# Pakfav7.net
KiCad netlist of a schematic drawn in EAGLE
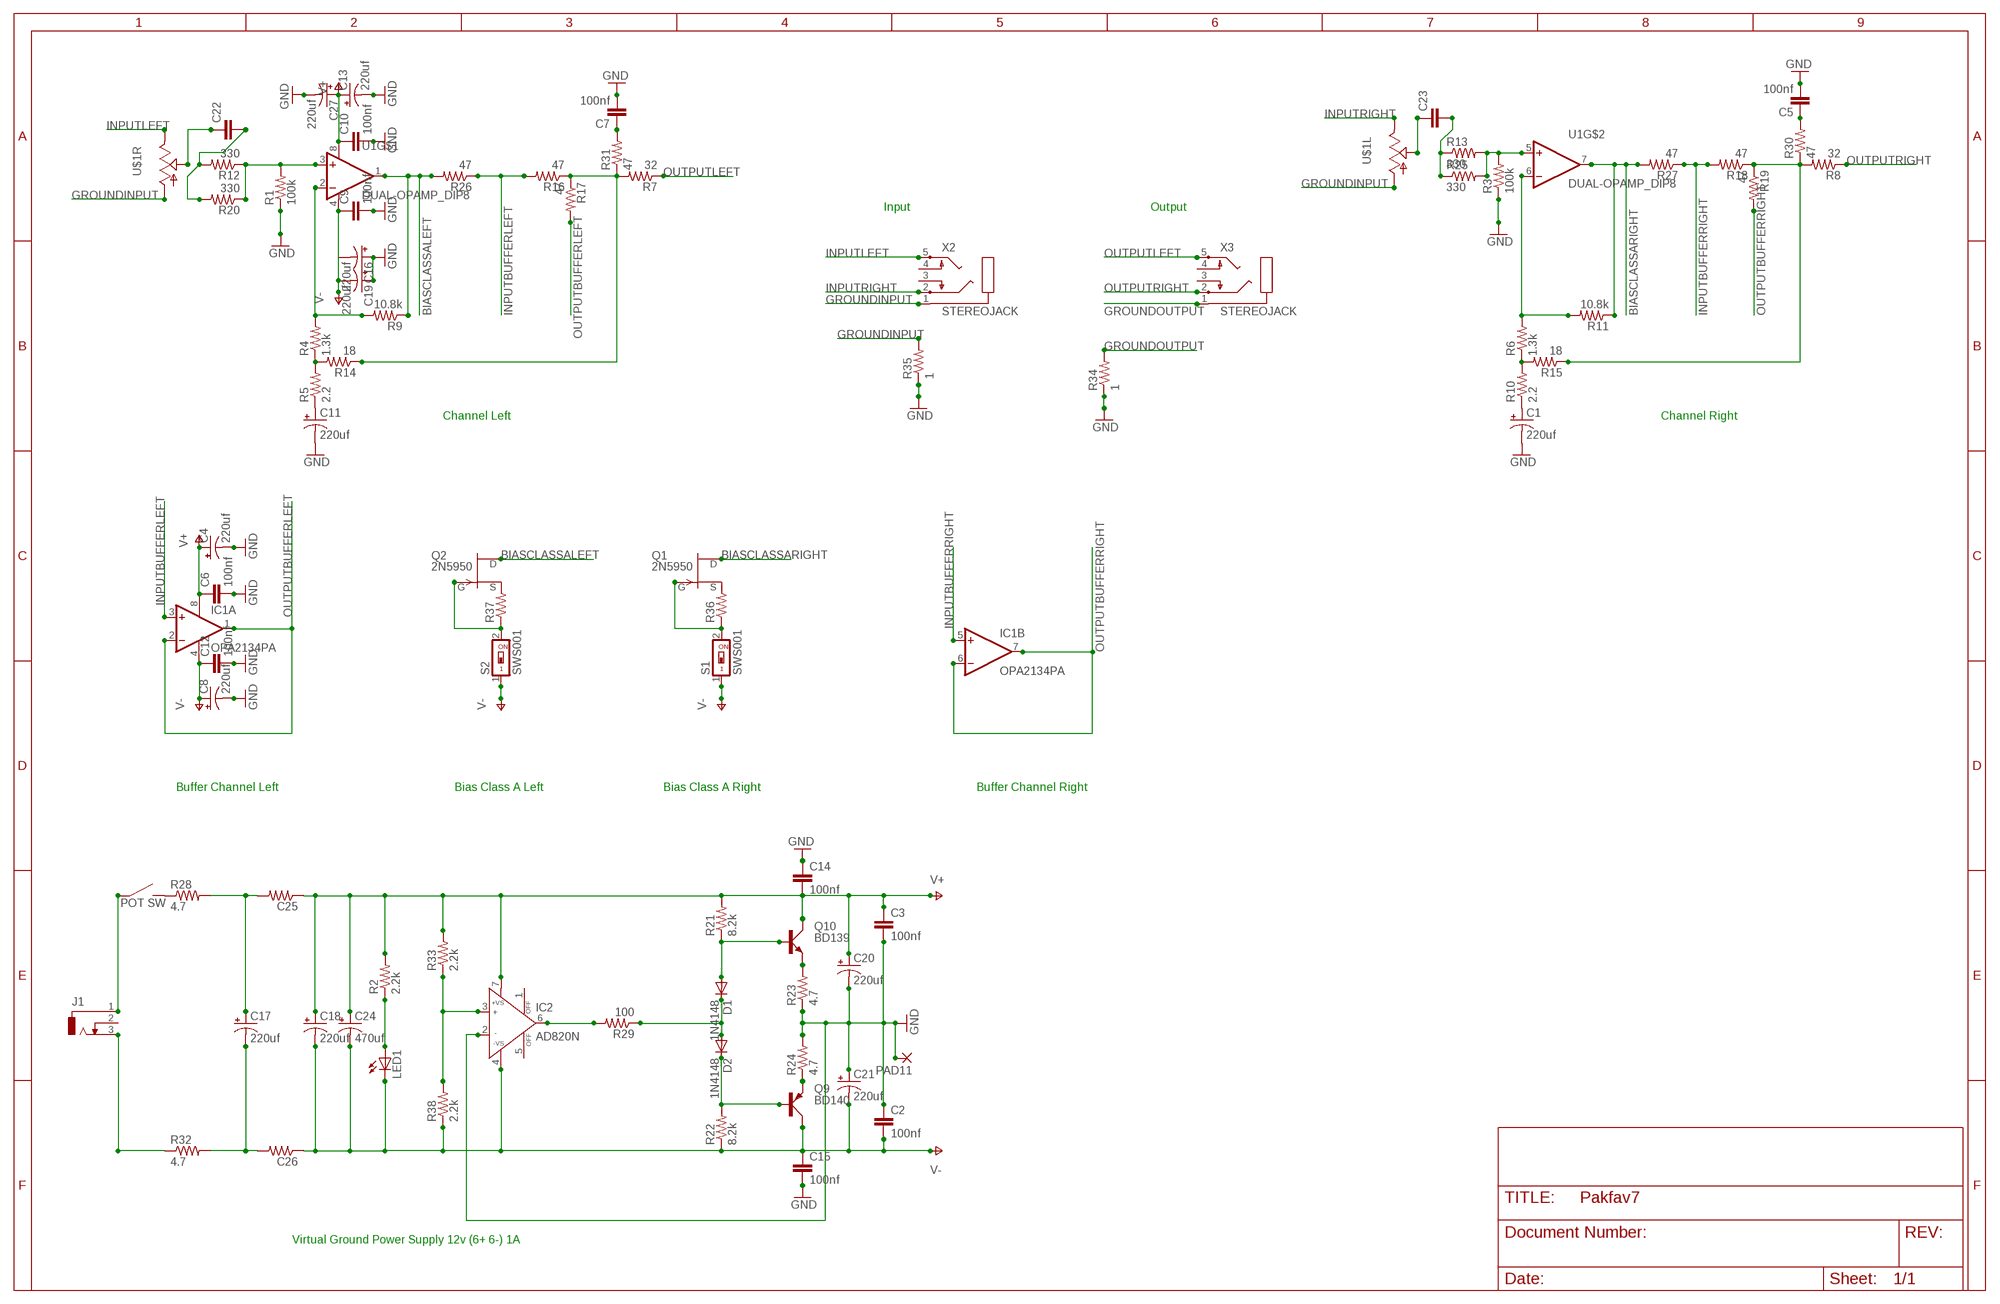
[diagram p0: schematic, sheet 1]

(export (version "E")
  (design (tool "Eeschema 10.0.6"))
  (components
    (comp (ref "C1")
      (value "220uf")
      (footprint "eagle-import:E5-10,5")
      (libsource (lib "eagle-import") (part "CPOL-USE5-10.5"))
    )
    (comp (ref "C2")
      (value "100nf")
      (footprint "eagle-import:C5B2.5")
      (libsource (lib "eagle-import") (part "C5/2.5"))
    )
    (comp (ref "C3")
      (value "100nf")
      (footprint "eagle-import:C5B2.5")
      (libsource (lib "eagle-import") (part "C5/2.5"))
    )
    (comp (ref "C4")
      (value "220uf")
      (footprint "eagle-import:E5-10,5")
      (libsource (lib "eagle-import") (part "CPOL-USE5-10.5"))
    )
    (comp (ref "C5")
      (value "100nf")
      (footprint "eagle-import:C5B2.5")
      (libsource (lib "eagle-import") (part "C5/2.5"))
    )
    (comp (ref "C6")
      (value "100nf")
      (footprint "eagle-import:C5B2.5")
      (libsource (lib "eagle-import") (part "C5/2.5"))
    )
    (comp (ref "C7")
      (value "100nf")
      (footprint "eagle-import:C5B2.5")
      (libsource (lib "eagle-import") (part "C5/2.5"))
    )
    (comp (ref "C8")
      (value "220uf")
      (footprint "eagle-import:E5-10,5")
      (libsource (lib "eagle-import") (part "CPOL-USE5-10.5"))
    )
    (comp (ref "C9")
      (value "100nf")
      (footprint "eagle-import:C5B2.5")
      (libsource (lib "eagle-import") (part "C5/2.5"))
    )
    (comp (ref "C10")
      (value "100nf")
      (footprint "eagle-import:C5B2.5")
      (libsource (lib "eagle-import") (part "C5/2.5"))
    )
    (comp (ref "C11")
      (value "220uf")
      (footprint "eagle-import:E5-10,5")
      (libsource (lib "eagle-import") (part "CPOL-USE5-10.5"))
    )
    (comp (ref "C12")
      (value "100nf")
      (footprint "eagle-import:C5B2.5")
      (libsource (lib "eagle-import") (part "C5/2.5"))
    )
    (comp (ref "C13")
      (value "220uf")
      (footprint "eagle-import:E5-10,5")
      (libsource (lib "eagle-import") (part "CPOL-USE5-10.5"))
    )
    (comp (ref "C14")
      (value "100nf")
      (footprint "eagle-import:C5B2.5")
      (libsource (lib "eagle-import") (part "C5/2.5"))
    )
    (comp (ref "C15")
      (value "100nf")
      (footprint "eagle-import:C5B2.5")
      (libsource (lib "eagle-import") (part "C5/2.5"))
    )
    (comp (ref "C16")
      (value "220uf")
      (footprint "eagle-import:E5-10,5")
      (libsource (lib "eagle-import") (part "CPOL-USE5-10.5"))
    )
    (comp (ref "C17")
      (value "220uf")
      (footprint "eagle-import:E3,5-10")
      (libsource (lib "eagle-import") (part "rcl_334_CPOL-USE3.5-10"))
    )
    (comp (ref "C18")
      (value "220uf")
      (footprint "eagle-import:E3,5-10")
      (libsource (lib "eagle-import") (part "rcl_334_CPOL-USE3.5-10"))
    )
    (comp (ref "C19")
      (value "220uf")
      (footprint "eagle-import:E5-10,5")
      (libsource (lib "eagle-import") (part "CPOL-USE5-10.5"))
    )
    (comp (ref "C20")
      (value "220uf")
      (footprint "eagle-import:D_7343-31R")
      (libsource (lib "eagle-import") (part "rcl_334_CPOL-USD/7343-31R"))
    )
    (comp (ref "C21")
      (value "220uf")
      (footprint "eagle-import:D_7343-31R")
      (libsource (lib "eagle-import") (part "rcl_334_CPOL-USD/7343-31R"))
    )
    (comp (ref "C22")
      (value "C22/6")
      (footprint "eagle-import:C22.5B6")
      (libsource (lib "eagle-import") (part "capacitor-wima_116_C22/6"))
    )
    (comp (ref "C23")
      (value "C22/6")
      (footprint "eagle-import:C22.5B6")
      (libsource (lib "eagle-import") (part "capacitor-wima_116_C22/6"))
    )
    (comp (ref "C24")
      (value "470uf")
      (footprint "eagle-import:E5-10,5")
      (libsource (lib "eagle-import") (part "CPOL-USE5-10.5"))
    )
    (comp (ref "C25")
      (value "R-US_0207/12")
      (footprint "eagle-import:0207_12")
      (libsource (lib "eagle-import") (part "resistor_348_R-US_0207/12"))
    )
    (comp (ref "C26")
      (value "R-US_0207/12")
      (footprint "eagle-import:0207_12")
      (libsource (lib "eagle-import") (part "resistor_348_R-US_0207/12"))
    )
    (comp (ref "C27")
      (value "220uf")
      (footprint "eagle-import:E5-10,5")
      (libsource (lib "eagle-import") (part "CPOL-USE5-10.5"))
    )
    (comp (ref "D1")
      (value "1N4148")
      (footprint "eagle-import:DO35-7")
      (libsource (lib "eagle-import") (part "1N4148DO35-7"))
    )
    (comp (ref "D2")
      (value "1N4148")
      (footprint "eagle-import:DO35-7")
      (libsource (lib "eagle-import") (part "1N4148DO35-7"))
    )
    (comp (ref "IC1")
      (value "OPA2134PA")
      (footprint "eagle-import:DIL08")
      (libsource (lib "eagle-import") (part "OPA2PA134"))
    )
    (comp (ref "IC2")
      (value "AD820N")
      (footprint "eagle-import:DIL08")
      (libsource (lib "eagle-import") (part "AD820N"))
    )
    (comp (ref "J1")
      (value "DCJ0303")
      (footprint "eagle-import:DCJ0303")
      (libsource (lib "eagle-import") (part "DCJ0303"))
    )
    (comp (ref "LED1")
      (value "LED3MM")
      (footprint "eagle-import:LED3MM")
      (libsource (lib "eagle-import") (part "LED3MM"))
    )
    (comp (ref "PAD11")
      (value "1,6/0,9")
      (footprint "eagle-import:1,6_0,9")
      (libsource (lib "eagle-import") (part "1,6/0,9"))
    )
    (comp (ref "Q1")
      (value "2N5950")
      (footprint "eagle-import:TO-92")
      (libsource (lib "eagle-import") (part "2N5950"))
    )
    (comp (ref "Q2")
      (value "2N5950")
      (footprint "eagle-import:TO-92")
      (libsource (lib "eagle-import") (part "2N5950"))
    )
    (comp (ref "Q9")
      (value "BD140")
      (footprint "eagle-import:TO126AV")
      (libsource (lib "eagle-import") (part "BD140"))
    )
    (comp (ref "Q10")
      (value "BD139")
      (footprint "eagle-import:TO126AV")
      (libsource (lib "eagle-import") (part "BD139"))
    )
    (comp (ref "R1")
      (value "100k")
      (footprint "eagle-import:0207_10")
      (libsource (lib "eagle-import") (part "R-US_0207/10"))
    )
    (comp (ref "R2")
      (value "2.2k")
      (footprint "eagle-import:0207_10")
      (libsource (lib "eagle-import") (part "resistor@1_R-US_0207/10"))
    )
    (comp (ref "R3")
      (value "100k")
      (footprint "eagle-import:0207_10")
      (libsource (lib "eagle-import") (part "R-US_0207/10"))
    )
    (comp (ref "R4")
      (value "1.3k")
      (footprint "eagle-import:0207_10")
      (libsource (lib "eagle-import") (part "R-US_0207/10"))
    )
    (comp (ref "R5")
      (value "2.2")
      (footprint "eagle-import:0204_5")
      (libsource (lib "eagle-import") (part "resistor_348_R-US_0204/5"))
    )
    (comp (ref "R6")
      (value "1.3k")
      (footprint "eagle-import:0207_10")
      (libsource (lib "eagle-import") (part "R-US_0207/10"))
    )
    (comp (ref "R7")
      (value "32")
      (footprint "eagle-import:0207_12")
      (libsource (lib "eagle-import") (part "resistor@1_R-US_0207/12"))
    )
    (comp (ref "R8")
      (value "32")
      (footprint "eagle-import:0207_12")
      (libsource (lib "eagle-import") (part "resistor@1_R-US_0207/12"))
    )
    (comp (ref "R9")
      (value "10.8k")
      (footprint "eagle-import:0207_10")
      (libsource (lib "eagle-import") (part "R-US_0207/10"))
    )
    (comp (ref "R10")
      (value "2.2")
      (footprint "eagle-import:0204_5")
      (libsource (lib "eagle-import") (part "resistor_348_R-US_0204/5"))
    )
    (comp (ref "R11")
      (value "10.8k")
      (footprint "eagle-import:0207_10")
      (libsource (lib "eagle-import") (part "R-US_0207/10"))
    )
    (comp (ref "R12")
      (value "330")
      (footprint "eagle-import:0207_10")
      (libsource (lib "eagle-import") (part "R-US_0207/10"))
    )
    (comp (ref "R13")
      (value "330")
      (footprint "eagle-import:0207_10")
      (libsource (lib "eagle-import") (part "R-US_0207/10"))
    )
    (comp (ref "R14")
      (value "18")
      (footprint "eagle-import:0207_12")
      (libsource (lib "eagle-import") (part "resistor@1_R-US_0207/12"))
    )
    (comp (ref "R15")
      (value "18")
      (footprint "eagle-import:0207_12")
      (libsource (lib "eagle-import") (part "resistor@1_R-US_0207/12"))
    )
    (comp (ref "R16")
      (value "47")
      (footprint "eagle-import:0207_12")
      (libsource (lib "eagle-import") (part "resistor@1_R-US_0207/12"))
    )
    (comp (ref "R17")
      (value "47")
      (footprint "eagle-import:0207_12")
      (libsource (lib "eagle-import") (part "resistor@1_R-US_0207/12"))
    )
    (comp (ref "R18")
      (value "47")
      (footprint "eagle-import:0207_12")
      (libsource (lib "eagle-import") (part "resistor@1_R-US_0207/12"))
    )
    (comp (ref "R19")
      (value "47")
      (footprint "eagle-import:0207_12")
      (libsource (lib "eagle-import") (part "resistor@1_R-US_0207/12"))
    )
    (comp (ref "R20")
      (value "330")
      (footprint "eagle-import:0207_10")
      (libsource (lib "eagle-import") (part "R-US_0207/10"))
    )
    (comp (ref "R21")
      (value "8.2k")
      (footprint "eagle-import:0207_10")
      (libsource (lib "eagle-import") (part "resistor@1_R-US_0207/10"))
    )
    (comp (ref "R22")
      (value "8.2k")
      (footprint "eagle-import:0207_10")
      (libsource (lib "eagle-import") (part "resistor@1_R-US_0207/10"))
    )
    (comp (ref "R23")
      (value "4.7")
      (footprint "eagle-import:0207_10")
      (libsource (lib "eagle-import") (part "resistor@1_R-US_0207/10"))
    )
    (comp (ref "R24")
      (value "4.7")
      (footprint "eagle-import:0207_10")
      (libsource (lib "eagle-import") (part "resistor@1_R-US_0207/10"))
    )
    (comp (ref "R25")
      (value "330")
      (footprint "eagle-import:0207_10")
      (libsource (lib "eagle-import") (part "R-US_0207/10"))
    )
    (comp (ref "R26")
      (value "47")
      (footprint "eagle-import:0207_10")
      (libsource (lib "eagle-import") (part "resistor@1_R-US_0207/10"))
    )
    (comp (ref "R27")
      (value "47")
      (footprint "eagle-import:0207_10")
      (libsource (lib "eagle-import") (part "resistor@1_R-US_0207/10"))
    )
    (comp (ref "R28")
      (value "4.7")
      (footprint "eagle-import:0207_10")
      (libsource (lib "eagle-import") (part "resistor@1_R-US_0207/10"))
    )
    (comp (ref "R29")
      (value "100")
      (footprint "eagle-import:0207_10")
      (libsource (lib "eagle-import") (part "resistor@1_R-US_0207/10"))
    )
    (comp (ref "R30")
      (value "47")
      (footprint "eagle-import:0207_7")
      (libsource (lib "eagle-import") (part "R-US_0207/7"))
    )
    (comp (ref "R31")
      (value "47")
      (footprint "eagle-import:0207_7")
      (libsource (lib "eagle-import") (part "R-US_0207/7"))
    )
    (comp (ref "R32")
      (value "4.7")
      (footprint "eagle-import:0207_10")
      (libsource (lib "eagle-import") (part "resistor@1_R-US_0207/10"))
    )
    (comp (ref "R33")
      (value "2.2k")
      (footprint "eagle-import:0207_10")
      (libsource (lib "eagle-import") (part "resistor@1_R-US_0207/10"))
    )
    (comp (ref "R34")
      (value "1")
      (footprint "eagle-import:0207_7")
      (libsource (lib "eagle-import") (part "R-US_0207/7"))
    )
    (comp (ref "R35")
      (value "1")
      (footprint "eagle-import:0207_7")
      (libsource (lib "eagle-import") (part "R-US_0207/7"))
    )
    (comp (ref "R36")
      (value "R-US_0204/5")
      (footprint "eagle-import:0204_5")
      (libsource (lib "eagle-import") (part "resistor@1_R-US_0204/5"))
    )
    (comp (ref "R37")
      (value "R-US_0204/5")
      (footprint "eagle-import:0204_5")
      (libsource (lib "eagle-import") (part "resistor@1_R-US_0204/5"))
    )
    (comp (ref "R38")
      (value "2.2k")
      (footprint "eagle-import:0207_10")
      (libsource (lib "eagle-import") (part "resistor@1_R-US_0207/10"))
    )
    (comp (ref "S1")
      (value "SWS001")
      (footprint "eagle-import:SMS-001")
      (libsource (lib "eagle-import") (part "SWS001"))
    )
    (comp (ref "S2")
      (value "SWS001")
      (footprint "eagle-import:SMS-001")
      (libsource (lib "eagle-import") (part "SWS001"))
    )
    (comp (ref "U$1")
      (value "ALPS_RK0971221Z05")
      (footprint "eagle-import:ALPS_RK0971221Z0X")
      (libsource (lib "eagle-import") (part "ALPS_RK0971221Z05"))
    )
    (comp (ref "U1")
      (value "DUAL-OPAMP_DIP8")
      (footprint "eagle-import:DIP-8")
      (libsource (lib "eagle-import") (part "DUAL-OPAMP_DIP8"))
    )
    (comp (ref "X2")
      (value "STEREOJACK")
      (footprint "eagle-import:STX3100")
      (libsource (lib "eagle-import") (part "STEREOJACK"))
    )
    (comp (ref "X3")
      (value "STEREOJACK")
      (footprint "eagle-import:STX3100")
      (libsource (lib "eagle-import") (part "STEREOJACK"))
    )
  )
  (nets
    (net (code "1") (name "/BIASCLASSALEFT") (class "Default")
      (node (ref "Q2") (pin "3") (pinfunction "D_3") (pintype "passive"))
      (node (ref "R26") (pin "2") (pinfunction "2_2") (pintype "passive"))
      (node (ref "R9") (pin "1") (pinfunction "1_1") (pintype "passive"))
      (node (ref "U1") (pin "1") (pinfunction "OUT_1") (pintype "output"))
    )
    (net (code "2") (name "/BIASCLASSARIGHT") (class "Default")
      (node (ref "Q1") (pin "3") (pinfunction "D_3") (pintype "passive"))
      (node (ref "R11") (pin "1") (pinfunction "1_1") (pintype "passive"))
      (node (ref "R27") (pin "2") (pinfunction "2_2") (pintype "passive"))
      (node (ref "U1") (pin "7") (pinfunction "OUT_7") (pintype "output"))
    )
    (net (code "3") (name "/GROUNDINPUT") (class "Default")
      (node (ref "R35") (pin "2") (pinfunction "2_2") (pintype "passive"))
      (node (ref "U$1") (pin "G1") (pinfunction "1_G1") (pintype "passive"))
      (node (ref "U$1") (pin "G2") (pinfunction "1_G2") (pintype "passive"))
      (node (ref "X2") (pin "1") (pinfunction "1_1") (pintype "passive"))
    )
    (net (code "4") (name "/GROUNDOUTPUT") (class "Default")
      (node (ref "R34") (pin "2") (pinfunction "2_2") (pintype "passive"))
      (node (ref "X3") (pin "1") (pinfunction "1_1") (pintype "passive"))
    )
    (net (code "5") (name "/INPUTBUFFERLEFT") (class "Default")
      (node (ref "IC1") (pin "3") (pinfunction "+IN_3") (pintype "input"))
      (node (ref "R16") (pin "2") (pinfunction "2_2") (pintype "passive"))
      (node (ref "R26") (pin "1") (pinfunction "1_1") (pintype "passive"))
    )
    (net (code "6") (name "/INPUTBUFFERRIGHT") (class "Default")
      (node (ref "IC1") (pin "5") (pinfunction "+IN_5") (pintype "input"))
      (node (ref "R18") (pin "2") (pinfunction "2_2") (pintype "passive"))
      (node (ref "R27") (pin "1") (pinfunction "1_1") (pintype "passive"))
    )
    (net (code "7") (name "/INPUTLEFT") (class "Default")
      (node (ref "U$1") (pin "I2") (pinfunction "3_I2") (pintype "passive"))
      (node (ref "X2") (pin "5") (pinfunction "5_5") (pintype "passive"))
    )
    (net (code "8") (name "/INPUTRIGHT") (class "Default")
      (node (ref "U$1") (pin "I1") (pinfunction "3_I1") (pintype "passive"))
      (node (ref "X2") (pin "2") (pinfunction "2_2") (pintype "passive"))
    )
    (net (code "9") (name "/OUTPUTBUFFERLEFT") (class "Default")
      (node (ref "IC1") (pin "1") (pinfunction "OUT_1") (pintype "output"))
      (node (ref "IC1") (pin "2") (pinfunction "-IN_2") (pintype "input"))
      (node (ref "R17") (pin "2") (pinfunction "2_2") (pintype "passive"))
    )
    (net (code "10") (name "/OUTPUTBUFFERRIGHT") (class "Default")
      (node (ref "IC1") (pin "6") (pinfunction "-IN_6") (pintype "input"))
      (node (ref "IC1") (pin "7") (pinfunction "OUT_7") (pintype "output"))
      (node (ref "R19") (pin "2") (pinfunction "2_2") (pintype "passive"))
    )
    (net (code "11") (name "/OUTPUTLEFT") (class "Default")
      (node (ref "R7") (pin "1") (pinfunction "1_1") (pintype "passive"))
      (node (ref "X3") (pin "5") (pinfunction "5_5") (pintype "passive"))
    )
    (net (code "12") (name "/OUTPUTRIGHT") (class "Default")
      (node (ref "R8") (pin "1") (pinfunction "1_1") (pintype "passive"))
      (node (ref "X3") (pin "2") (pinfunction "2_2") (pintype "passive"))
    )
    (net (code "13") (name "GND") (class "Default")
      (node (ref "C1") (pin "-") (pinfunction "-_-") (pintype "passive"))
      (node (ref "C10") (pin "2") (pinfunction "2_2") (pintype "passive"))
      (node (ref "C11") (pin "-") (pinfunction "-_-") (pintype "passive"))
      (node (ref "C12") (pin "2") (pinfunction "2_2") (pintype "passive"))
      (node (ref "C13") (pin "-") (pinfunction "-_-") (pintype "passive"))
      (node (ref "C14") (pin "1") (pinfunction "1_1") (pintype "passive"))
      (node (ref "C15") (pin "2") (pinfunction "2_2") (pintype "passive"))
      (node (ref "C16") (pin "+") (pinfunction "+_+") (pintype "passive"))
      (node (ref "C19") (pin "+") (pinfunction "+_+") (pintype "passive"))
      (node (ref "C2") (pin "1") (pinfunction "1_1") (pintype "passive"))
      (node (ref "C20") (pin "-") (pinfunction "-_-") (pintype "passive"))
      (node (ref "C21") (pin "+") (pinfunction "+_+") (pintype "passive"))
      (node (ref "C27") (pin "-") (pinfunction "-_-") (pintype "passive"))
      (node (ref "C3") (pin "2") (pinfunction "2_2") (pintype "passive"))
      (node (ref "C4") (pin "-") (pinfunction "-_-") (pintype "passive"))
      (node (ref "C5") (pin "2") (pinfunction "2_2") (pintype "passive"))
      (node (ref "C6") (pin "2") (pinfunction "2_2") (pintype "passive"))
      (node (ref "C7") (pin "2") (pinfunction "2_2") (pintype "passive"))
      (node (ref "C8") (pin "-") (pinfunction "-_-") (pintype "passive"))
      (node (ref "C9") (pin "2") (pinfunction "2_2") (pintype "passive"))
      (node (ref "IC2") (pin "2") (pinfunction "IN-_2") (pintype "input"))
      (node (ref "PAD11") (pin "1") (pinfunction "P_1") (pintype "passive"))
      (node (ref "R1") (pin "1") (pinfunction "1_1") (pintype "passive"))
      (node (ref "R23") (pin "1") (pinfunction "1_1") (pintype "passive"))
      (node (ref "R24") (pin "2") (pinfunction "2_2") (pintype "passive"))
      (node (ref "R3") (pin "1") (pinfunction "1_1") (pintype "passive"))
      (node (ref "R34") (pin "1") (pinfunction "1_1") (pintype "passive"))
      (node (ref "R35") (pin "1") (pinfunction "1_1") (pintype "passive"))
    )
    (net (code "14") (name "Net-(C1-Pad+)") (class "Default")
      (node (ref "C1") (pin "+") (pinfunction "+_+") (pintype "passive"))
      (node (ref "R10") (pin "1") (pinfunction "1_1") (pintype "passive"))
    )
    (net (code "15") (name "Net-(C5-Pad1)") (class "Default")
      (node (ref "C5") (pin "1") (pinfunction "1_1") (pintype "passive"))
      (node (ref "R30") (pin "2") (pinfunction "2_2") (pintype "passive"))
    )
    (net (code "16") (name "Net-(C7-Pad1)") (class "Default")
      (node (ref "C7") (pin "1") (pinfunction "1_1") (pintype "passive"))
      (node (ref "R31") (pin "2") (pinfunction "2_2") (pintype "passive"))
    )
    (net (code "17") (name "Net-(C11-Pad+)") (class "Default")
      (node (ref "C11") (pin "+") (pinfunction "+_+") (pintype "passive"))
      (node (ref "R5") (pin "1") (pinfunction "1_1") (pintype "passive"))
    )
    (net (code "18") (name "Net-(C17-Pad+)") (class "Default")
      (node (ref "C17") (pin "+") (pinfunction "+_+") (pintype "passive"))
      (node (ref "C25") (pin "2") (pinfunction "2_2") (pintype "passive"))
      (node (ref "R28") (pin "2") (pinfunction "2_2") (pintype "passive"))
    )
    (net (code "19") (name "Net-(C17-Pad-)") (class "Default")
      (node (ref "C17") (pin "-") (pinfunction "-_-") (pintype "passive"))
      (node (ref "C26") (pin "2") (pinfunction "2_2") (pintype "passive"))
      (node (ref "R32") (pin "2") (pinfunction "2_2") (pintype "passive"))
    )
    (net (code "20") (name "Net-(C22-Pad2)") (class "Default")
      (node (ref "C22") (pin "2") (pinfunction "2_2") (pintype "passive"))
      (node (ref "R12") (pin "2") (pinfunction "2_2") (pintype "passive"))
      (node (ref "R20") (pin "2") (pinfunction "2_2") (pintype "passive"))
    )
    (net (code "21") (name "Net-(C23-Pad2)") (class "Default")
      (node (ref "C23") (pin "2") (pinfunction "2_2") (pintype "passive"))
      (node (ref "R13") (pin "1") (pinfunction "1_1") (pintype "passive"))
      (node (ref "R25") (pin "1") (pinfunction "1_1") (pintype "passive"))
    )
    (net (code "22") (name "Net-(D1-PadA)") (class "Default")
      (node (ref "D1") (pin "A") (pinfunction "A_A") (pintype "passive"))
      (node (ref "Q10") (pin "B") (pinfunction "B_B") (pintype "passive"))
      (node (ref "R21") (pin "1") (pinfunction "1_1") (pintype "passive"))
    )
    (net (code "23") (name "Net-(D1-PadC)") (class "Default")
      (node (ref "D1") (pin "C") (pinfunction "C_C") (pintype "passive"))
      (node (ref "D2") (pin "A") (pinfunction "A_A") (pintype "passive"))
      (node (ref "R29") (pin "1") (pinfunction "1_1") (pintype "passive"))
    )
    (net (code "24") (name "Net-(D2-PadC)") (class "Default")
      (node (ref "D2") (pin "C") (pinfunction "C_C") (pintype "passive"))
      (node (ref "Q9") (pin "B") (pinfunction "B_B") (pintype "passive"))
      (node (ref "R22") (pin "2") (pinfunction "2_2") (pintype "passive"))
    )
    (net (code "25") (name "Net-(IC2-IN+)") (class "Default")
      (node (ref "IC2") (pin "3") (pinfunction "IN+_3") (pintype "input"))
      (node (ref "R33") (pin "1") (pinfunction "1_1") (pintype "passive"))
      (node (ref "R38") (pin "2") (pinfunction "2_2") (pintype "passive"))
    )
    (net (code "26") (name "Net-(IC2-OUT)") (class "Default")
      (node (ref "IC2") (pin "6") (pinfunction "OUT_6") (pintype "output"))
      (node (ref "R29") (pin "2") (pinfunction "2_2") (pintype "passive"))
    )
    (net (code "27") (name "Net-(J1-Pad1)") (class "Default")
      (node (ref "J1") (pin "1") (pinfunction "1_1") (pintype "passive"))
      (node (ref "U$1") (pin "S1") (pinfunction "S1_S1") (pintype "power_in"))
    )
    (net (code "28") (name "Net-(J1-Pad3)") (class "Default")
      (node (ref "J1") (pin "3") (pinfunction "3_3") (pintype "passive"))
      (node (ref "R32") (pin "1") (pinfunction "1_1") (pintype "passive"))
    )
    (net (code "29") (name "Net-(LED1-PadA)") (class "Default")
      (node (ref "LED1") (pin "A") (pinfunction "A_A") (pintype "passive"))
      (node (ref "R2") (pin "1") (pinfunction "1_1") (pintype "passive"))
    )
    (net (code "30") (name "Net-(Q1-G)") (class "Default")
      (node (ref "Q1") (pin "1") (pinfunction "G_1") (pintype "passive"))
      (node (ref "R36") (pin "1") (pinfunction "1_1") (pintype "passive"))
      (node (ref "S1") (pin "2") (pinfunction "2_2") (pintype "passive"))
    )
    (net (code "31") (name "Net-(Q1-S)") (class "Default")
      (node (ref "Q1") (pin "2") (pinfunction "S_2") (pintype "passive"))
      (node (ref "R36") (pin "2") (pinfunction "2_2") (pintype "passive"))
    )
    (net (code "32") (name "Net-(Q2-G)") (class "Default")
      (node (ref "Q2") (pin "1") (pinfunction "G_1") (pintype "passive"))
      (node (ref "R37") (pin "1") (pinfunction "1_1") (pintype "passive"))
      (node (ref "S2") (pin "2") (pinfunction "2_2") (pintype "passive"))
    )
    (net (code "33") (name "Net-(Q2-S)") (class "Default")
      (node (ref "Q2") (pin "2") (pinfunction "S_2") (pintype "passive"))
      (node (ref "R37") (pin "2") (pinfunction "2_2") (pintype "passive"))
    )
    (net (code "34") (name "Net-(Q9-PadE)") (class "Default")
      (node (ref "Q9") (pin "E") (pinfunction "E_E") (pintype "passive"))
      (node (ref "R24") (pin "1") (pinfunction "1_1") (pintype "passive"))
    )
    (net (code "35") (name "Net-(Q10-PadE)") (class "Default")
      (node (ref "Q10") (pin "E") (pinfunction "E_E") (pintype "passive"))
      (node (ref "R23") (pin "2") (pinfunction "2_2") (pintype "passive"))
    )
    (net (code "36") (name "Net-(R10-Pad2)") (class "Default")
      (node (ref "R10") (pin "2") (pinfunction "2_2") (pintype "passive"))
      (node (ref "R15") (pin "2") (pinfunction "2_2") (pintype "passive"))
      (node (ref "R6") (pin "1") (pinfunction "1_1") (pintype "passive"))
    )
    (net (code "37") (name "Net-(R14-Pad1)") (class "Default")
      (node (ref "R14") (pin "1") (pinfunction "1_1") (pintype "passive"))
      (node (ref "R16") (pin "1") (pinfunction "1_1") (pintype "passive"))
      (node (ref "R17") (pin "1") (pinfunction "1_1") (pintype "passive"))
      (node (ref "R31") (pin "1") (pinfunction "1_1") (pintype "passive"))
      (node (ref "R7") (pin "2") (pinfunction "2_2") (pintype "passive"))
    )
    (net (code "38") (name "Net-(R14-Pad2)") (class "Default")
      (node (ref "R14") (pin "2") (pinfunction "2_2") (pintype "passive"))
      (node (ref "R4") (pin "1") (pinfunction "1_1") (pintype "passive"))
      (node (ref "R5") (pin "2") (pinfunction "2_2") (pintype "passive"))
    )
    (net (code "39") (name "Net-(R15-Pad1)") (class "Default")
      (node (ref "R15") (pin "1") (pinfunction "1_1") (pintype "passive"))
      (node (ref "R18") (pin "1") (pinfunction "1_1") (pintype "passive"))
      (node (ref "R19") (pin "1") (pinfunction "1_1") (pintype "passive"))
      (node (ref "R30") (pin "1") (pinfunction "1_1") (pintype "passive"))
      (node (ref "R8") (pin "2") (pinfunction "2_2") (pintype "passive"))
    )
    (net (code "40") (name "Net-(R28-Pad1)") (class "Default")
      (node (ref "R28") (pin "1") (pinfunction "1_1") (pintype "passive"))
      (node (ref "U$1") (pin "S2") (pinfunction "S2_S2") (pintype "power_in"))
    )
    (net (code "41") (name "Net-(U$1B-2)") (class "Default")
      (node (ref "C23") (pin "1") (pinfunction "1_1") (pintype "passive"))
      (node (ref "U$1") (pin "O1") (pinfunction "2_O1") (pintype "passive"))
    )
    (net (code "42") (name "Net-(U$1C-2)") (class "Default")
      (node (ref "C22") (pin "1") (pinfunction "1_1") (pintype "passive"))
      (node (ref "U$1") (pin "O2") (pinfunction "2_O2") (pintype "passive"))
    )
    (net (code "43") (name "Net-(U1A-+IN)") (class "Default")
      (node (ref "R1") (pin "2") (pinfunction "2_2") (pintype "passive"))
      (node (ref "R12") (pin "1") (pinfunction "1_1") (pintype "passive"))
      (node (ref "R20") (pin "1") (pinfunction "1_1") (pintype "passive"))
      (node (ref "U1") (pin "3") (pinfunction "+IN_3") (pintype "input"))
    )
    (net (code "44") (name "Net-(U1A--IN)") (class "Default")
      (node (ref "R4") (pin "2") (pinfunction "2_2") (pintype "passive"))
      (node (ref "R9") (pin "2") (pinfunction "2_2") (pintype "passive"))
      (node (ref "U1") (pin "2") (pinfunction "-IN_2") (pintype "input"))
    )
    (net (code "45") (name "Net-(U1B-+IN)") (class "Default")
      (node (ref "R13") (pin "2") (pinfunction "2_2") (pintype "passive"))
      (node (ref "R25") (pin "2") (pinfunction "2_2") (pintype "passive"))
      (node (ref "R3") (pin "2") (pinfunction "2_2") (pintype "passive"))
      (node (ref "U1") (pin "5") (pinfunction "+IN_5") (pintype "input"))
    )
    (net (code "46") (name "Net-(U1B--IN)") (class "Default")
      (node (ref "R11") (pin "2") (pinfunction "2_2") (pintype "passive"))
      (node (ref "R6") (pin "2") (pinfunction "2_2") (pintype "passive"))
      (node (ref "U1") (pin "6") (pinfunction "-IN_6") (pintype "input"))
    )
    (net (code "47") (name "V+") (class "Default")
      (node (ref "C10") (pin "1") (pinfunction "1_1") (pintype "passive"))
      (node (ref "C13") (pin "+") (pinfunction "+_+") (pintype "passive"))
      (node (ref "C14") (pin "2") (pinfunction "2_2") (pintype "passive"))
      (node (ref "C18") (pin "+") (pinfunction "+_+") (pintype "passive"))
      (node (ref "C20") (pin "+") (pinfunction "+_+") (pintype "passive"))
      (node (ref "C24") (pin "+") (pinfunction "+_+") (pintype "passive"))
      (node (ref "C25") (pin "1") (pinfunction "1_1") (pintype "passive"))
      (node (ref "C27") (pin "+") (pinfunction "+_+") (pintype "passive"))
      (node (ref "C3") (pin "1") (pinfunction "1_1") (pintype "passive"))
      (node (ref "C4") (pin "+") (pinfunction "+_+") (pintype "passive"))
      (node (ref "C6") (pin "1") (pinfunction "1_1") (pintype "passive"))
      (node (ref "IC1") (pin "8") (pinfunction "V+_8") (pintype "power_in"))
      (node (ref "IC2") (pin "7") (pinfunction "+VS_7") (pintype "input"))
      (node (ref "Q10") (pin "C") (pinfunction "C_C") (pintype "passive"))
      (node (ref "R2") (pin "2") (pinfunction "2_2") (pintype "passive"))
      (node (ref "R21") (pin "2") (pinfunction "2_2") (pintype "passive"))
      (node (ref "R33") (pin "2") (pinfunction "2_2") (pintype "passive"))
      (node (ref "U1") (pin "8") (pinfunction "V+_8") (pintype "power_in"))
    )
    (net (code "48") (name "V-") (class "Default")
      (node (ref "C12") (pin "1") (pinfunction "1_1") (pintype "passive"))
      (node (ref "C15") (pin "1") (pinfunction "1_1") (pintype "passive"))
      (node (ref "C16") (pin "-") (pinfunction "-_-") (pintype "passive"))
      (node (ref "C18") (pin "-") (pinfunction "-_-") (pintype "passive"))
      (node (ref "C19") (pin "-") (pinfunction "-_-") (pintype "passive"))
      (node (ref "C2") (pin "2") (pinfunction "2_2") (pintype "passive"))
      (node (ref "C21") (pin "-") (pinfunction "-_-") (pintype "passive"))
      (node (ref "C24") (pin "-") (pinfunction "-_-") (pintype "passive"))
      (node (ref "C26") (pin "1") (pinfunction "1_1") (pintype "passive"))
      (node (ref "C8") (pin "+") (pinfunction "+_+") (pintype "passive"))
      (node (ref "C9") (pin "1") (pinfunction "1_1") (pintype "passive"))
      (node (ref "IC1") (pin "4") (pinfunction "V-_4") (pintype "power_in"))
      (node (ref "IC2") (pin "4") (pinfunction "-VS_4") (pintype "input"))
      (node (ref "LED1") (pin "K") (pinfunction "C_K") (pintype "passive"))
      (node (ref "Q9") (pin "C") (pinfunction "C_C") (pintype "passive"))
      (node (ref "R22") (pin "1") (pinfunction "1_1") (pintype "passive"))
      (node (ref "R38") (pin "1") (pinfunction "1_1") (pintype "passive"))
      (node (ref "S1") (pin "1") (pinfunction "1_1") (pintype "passive"))
      (node (ref "S2") (pin "1") (pinfunction "1_1") (pintype "passive"))
      (node (ref "U1") (pin "4") (pinfunction "V-_4") (pintype "power_in"))
    )
    (net (code "49") (name "unconnected-(IC2-OFF-Pad1)") (class "Default")
      (node (ref "IC2") (pin "1") (pinfunction "OFF_1") (pintype "passive"))
    )
    (net (code "50") (name "unconnected-(IC2-OFF-Pad5)") (class "Default")
      (node (ref "IC2") (pin "5") (pinfunction "OFF_5") (pintype "passive"))
    )
    (net (code "51") (name "unconnected-(J1-Pad2)") (class "Default")
      (node (ref "J1") (pin "2") (pinfunction "2_2") (pintype "passive"))
    )
    (net (code "52") (name "unconnected-(X2-Pad3)") (class "Default")
      (node (ref "X2") (pin "3") (pinfunction "3_3") (pintype "passive"))
    )
    (net (code "53") (name "unconnected-(X2-Pad4)") (class "Default")
      (node (ref "X2") (pin "4") (pinfunction "4_4") (pintype "passive"))
    )
    (net (code "54") (name "unconnected-(X3-Pad3)") (class "Default")
      (node (ref "X3") (pin "3") (pinfunction "3_3") (pintype "passive"))
    )
    (net (code "55") (name "unconnected-(X3-Pad4)") (class "Default")
      (node (ref "X3") (pin "4") (pinfunction "4_4") (pintype "passive"))
    )
  )
)
